# 9_pwm_out.net
KiCad netlist of a schematic drawn in Altium Designer
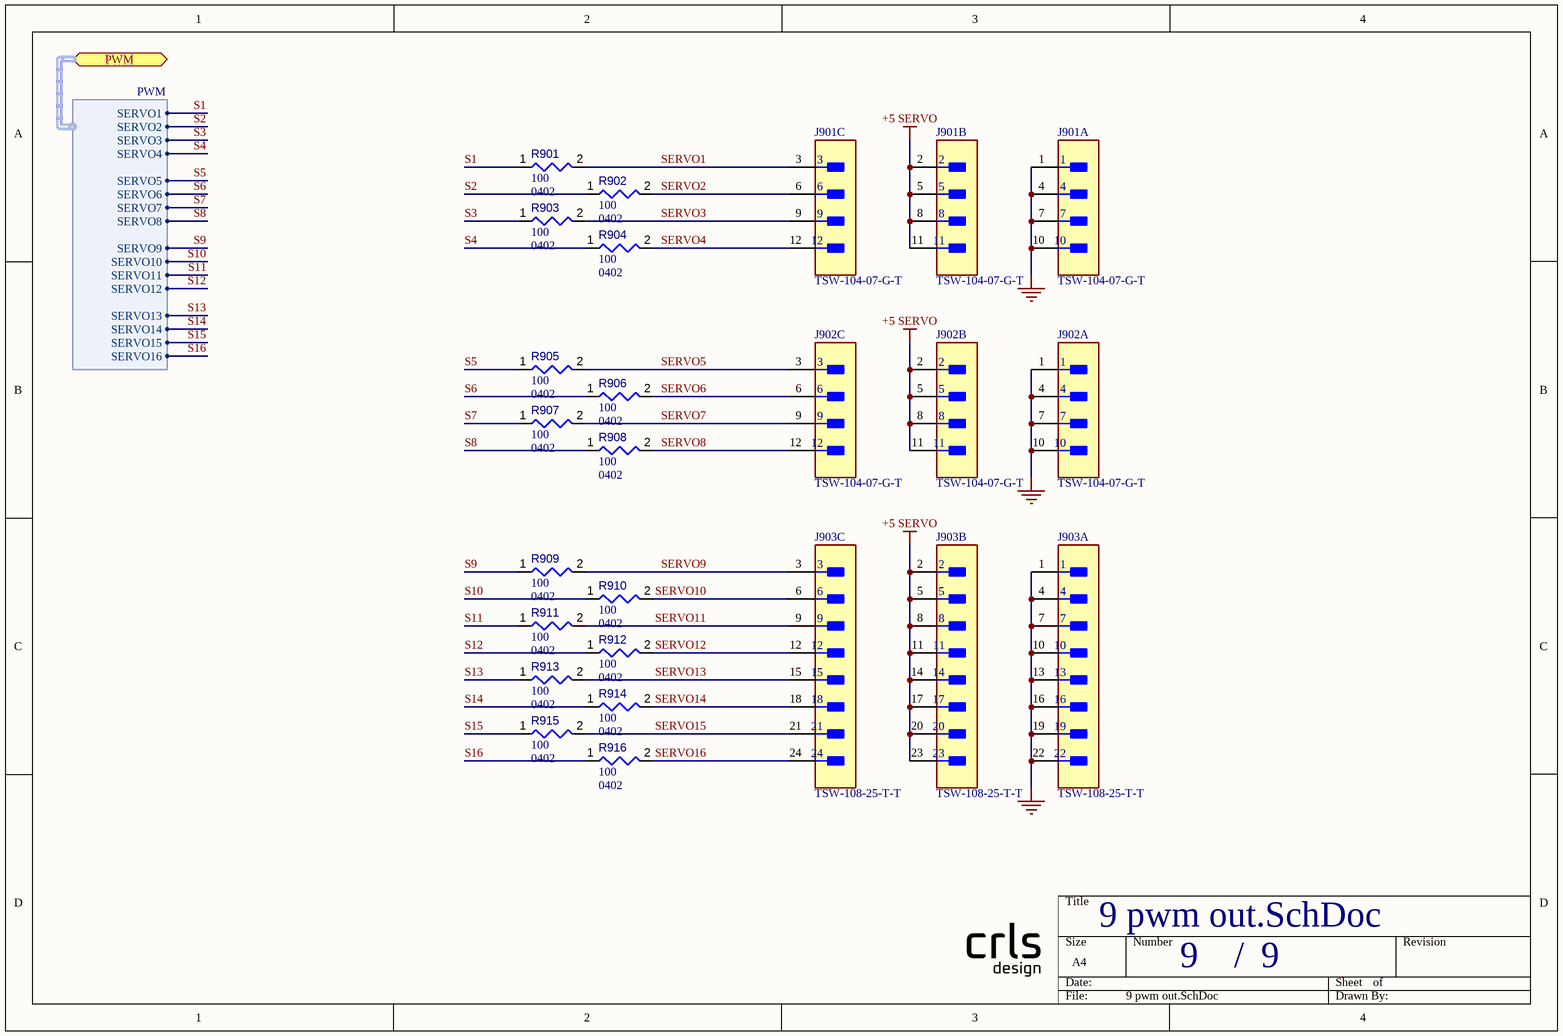
[diagram p0: 9 pwm out.SchDoc]

(export (version "E")
  (design (tool "Eeschema 10.0.6"))
  (components
    (comp (ref "J901")
      (value "TSW-104-07-G-T")
      (footprint "FP-TSW-104-07-G-T-MFG")
      (description "CONN HEADER VERT 12POS 2.54MM")
      (fields
        (field (name "MANUFACTURER") "Samtec")
        (field (name "OCTOPART") "https://octopart.com/tsw-104-07-g-t-samtec-8296723")
      )
      (libsource (lib "Altium Content Vault") (part "4835ffea529f644fb4232fae0277480"))
    )
    (comp (ref "J902")
      (value "TSW-104-07-G-T")
      (footprint "FP-TSW-104-07-G-T-MFG")
      (description "CONN HEADER VERT 12POS 2.54MM")
      (fields
        (field (name "MANUFACTURER") "Samtec")
        (field (name "OCTOPART") "https://octopart.com/tsw-104-07-g-t-samtec-8296723")
      )
      (libsource (lib "Altium Content Vault") (part "4835ffea529f644fb4232fae0277480"))
    )
    (comp (ref "J903")
      (value "TSW-108-25-T-T")
      (footprint "FP-TSW-108-25-T-T-MFG")
      (description "CONN HEADER VERT 24POS 2.54MM")
      (libsource (lib "Altium Content Vault") (part "1970d49fc78c71aba99bcf3589d2fd7"))
    )
    (comp (ref "R901")
      (value "100")
      (footprint "RESC0402(1005)_L")
      (description "Resistor")
      (fields
        (field (name "CASE/PACKAGE") "0402")
        (field (name "TOLERANCE") "1%")
        (field (name "Comment") "Resistors,0402,1%,100")
      )
      (libsource (lib "UBC Uncrewed Aircraft Systems") (part "RES-2"))
    )
    (comp (ref "R902")
      (value "100")
      (footprint "RESC0402(1005)_L")
      (description "Resistor")
      (fields
        (field (name "CASE/PACKAGE") "0402")
        (field (name "TOLERANCE") "1%")
        (field (name "Comment") "Resistors,0402,1%,100")
      )
      (libsource (lib "UBC Uncrewed Aircraft Systems") (part "RES-2"))
    )
    (comp (ref "R903")
      (value "100")
      (footprint "RESC0402(1005)_L")
      (description "Resistor")
      (fields
        (field (name "CASE/PACKAGE") "0402")
        (field (name "TOLERANCE") "1%")
        (field (name "Comment") "Resistors,0402,1%,100")
      )
      (libsource (lib "UBC Uncrewed Aircraft Systems") (part "RES-2"))
    )
    (comp (ref "R904")
      (value "100")
      (footprint "RESC0402(1005)_L")
      (description "Resistor")
      (fields
        (field (name "CASE/PACKAGE") "0402")
        (field (name "TOLERANCE") "1%")
        (field (name "Comment") "Resistors,0402,1%,100")
      )
      (libsource (lib "UBC Uncrewed Aircraft Systems") (part "RES-2"))
    )
    (comp (ref "R905")
      (value "100")
      (footprint "RESC0402(1005)_L")
      (description "Resistor")
      (fields
        (field (name "CASE/PACKAGE") "0402")
        (field (name "TOLERANCE") "1%")
        (field (name "Comment") "Resistors,0402,1%,100")
      )
      (libsource (lib "UBC Uncrewed Aircraft Systems") (part "RES-2"))
    )
    (comp (ref "R906")
      (value "100")
      (footprint "RESC0402(1005)_L")
      (description "Resistor")
      (fields
        (field (name "CASE/PACKAGE") "0402")
        (field (name "TOLERANCE") "1%")
        (field (name "Comment") "Resistors,0402,1%,100")
      )
      (libsource (lib "UBC Uncrewed Aircraft Systems") (part "RES-2"))
    )
    (comp (ref "R907")
      (value "100")
      (footprint "RESC0402(1005)_L")
      (description "Resistor")
      (fields
        (field (name "CASE/PACKAGE") "0402")
        (field (name "TOLERANCE") "1%")
        (field (name "Comment") "Resistors,0402,1%,100")
      )
      (libsource (lib "UBC Uncrewed Aircraft Systems") (part "RES-2"))
    )
    (comp (ref "R908")
      (value "100")
      (footprint "RESC0402(1005)_L")
      (description "Resistor")
      (fields
        (field (name "CASE/PACKAGE") "0402")
        (field (name "TOLERANCE") "1%")
        (field (name "Comment") "Resistors,0402,1%,100")
      )
      (libsource (lib "UBC Uncrewed Aircraft Systems") (part "RES-2"))
    )
    (comp (ref "R909")
      (value "100")
      (footprint "RESC0402(1005)_L")
      (description "Resistor")
      (fields
        (field (name "CASE/PACKAGE") "0402")
        (field (name "TOLERANCE") "1%")
        (field (name "Comment") "Resistors,0402,1%,100")
      )
      (libsource (lib "UBC Uncrewed Aircraft Systems") (part "RES-2"))
    )
    (comp (ref "R910")
      (value "100")
      (footprint "RESC0402(1005)_L")
      (description "Resistor")
      (fields
        (field (name "CASE/PACKAGE") "0402")
        (field (name "TOLERANCE") "1%")
        (field (name "Comment") "Resistors,0402,1%,100")
      )
      (libsource (lib "UBC Uncrewed Aircraft Systems") (part "RES-2"))
    )
    (comp (ref "R911")
      (value "100")
      (footprint "RESC0402(1005)_L")
      (description "Resistor")
      (fields
        (field (name "CASE/PACKAGE") "0402")
        (field (name "TOLERANCE") "1%")
        (field (name "Comment") "Resistors,0402,1%,100")
      )
      (libsource (lib "UBC Uncrewed Aircraft Systems") (part "RES-2"))
    )
    (comp (ref "R912")
      (value "100")
      (footprint "RESC0402(1005)_L")
      (description "Resistor")
      (fields
        (field (name "CASE/PACKAGE") "0402")
        (field (name "TOLERANCE") "1%")
        (field (name "Comment") "Resistors,0402,1%,100")
      )
      (libsource (lib "UBC Uncrewed Aircraft Systems") (part "RES-2"))
    )
    (comp (ref "R913")
      (value "100")
      (footprint "RESC0402(1005)_L")
      (description "Resistor")
      (fields
        (field (name "CASE/PACKAGE") "0402")
        (field (name "TOLERANCE") "1%")
        (field (name "Comment") "Resistors,0402,1%,100")
      )
      (libsource (lib "UBC Uncrewed Aircraft Systems") (part "RES-2"))
    )
    (comp (ref "R914")
      (value "100")
      (footprint "RESC0402(1005)_L")
      (description "Resistor")
      (fields
        (field (name "CASE/PACKAGE") "0402")
        (field (name "TOLERANCE") "1%")
        (field (name "Comment") "Resistors,0402,1%,100")
      )
      (libsource (lib "UBC Uncrewed Aircraft Systems") (part "RES-2"))
    )
    (comp (ref "R915")
      (value "100")
      (footprint "RESC0402(1005)_L")
      (description "Resistor")
      (fields
        (field (name "CASE/PACKAGE") "0402")
        (field (name "TOLERANCE") "1%")
        (field (name "Comment") "Resistors,0402,1%,100")
      )
      (libsource (lib "UBC Uncrewed Aircraft Systems") (part "RES-2"))
    )
    (comp (ref "R916")
      (value "100")
      (footprint "RESC0402(1005)_L")
      (description "Resistor")
      (fields
        (field (name "CASE/PACKAGE") "0402")
        (field (name "TOLERANCE") "1%")
        (field (name "Comment") "Resistors,0402,1%,100")
      )
      (libsource (lib "UBC Uncrewed Aircraft Systems") (part "RES-2"))
    )
  )
  (nets
    (net (code "2") (name "+5 SERVO") (class "Default")
      (node (ref "J901") (pin "11") (pinfunction "11_11") (pintype "passive"))
      (node (ref "J901") (pin "2") (pinfunction "2_2") (pintype "passive"))
      (node (ref "J901") (pin "5") (pinfunction "5_5") (pintype "passive"))
      (node (ref "J901") (pin "8") (pinfunction "8_8") (pintype "passive"))
      (node (ref "J902") (pin "11") (pinfunction "11_11") (pintype "passive"))
      (node (ref "J902") (pin "2") (pinfunction "2_2") (pintype "passive"))
      (node (ref "J902") (pin "5") (pinfunction "5_5") (pintype "passive"))
      (node (ref "J902") (pin "8") (pinfunction "8_8") (pintype "passive"))
      (node (ref "J903") (pin "11") (pinfunction "11_11") (pintype "passive"))
      (node (ref "J903") (pin "14") (pinfunction "14_14") (pintype "passive"))
      (node (ref "J903") (pin "17") (pinfunction "17_17") (pintype "passive"))
      (node (ref "J903") (pin "2") (pinfunction "2_2") (pintype "passive"))
      (node (ref "J903") (pin "20") (pinfunction "20_20") (pintype "passive"))
      (node (ref "J903") (pin "23") (pinfunction "23_23") (pintype "passive"))
      (node (ref "J903") (pin "5") (pinfunction "5_5") (pintype "passive"))
      (node (ref "J903") (pin "8") (pinfunction "8_8") (pintype "passive"))
    )
    (net (code "3") (name "/S1") (class "Default")
      (node (ref "R901") (pin "1") (pinfunction "1_1") (pintype "passive"))
    )
    (net (code "4") (name "/S2") (class "Default")
      (node (ref "R902") (pin "1") (pinfunction "1_1") (pintype "passive"))
    )
    (net (code "5") (name "/S3") (class "Default")
      (node (ref "R903") (pin "1") (pinfunction "1_1") (pintype "passive"))
    )
    (net (code "6") (name "/S4") (class "Default")
      (node (ref "R904") (pin "1") (pinfunction "1_1") (pintype "passive"))
    )
    (net (code "7") (name "/S5") (class "Default")
      (node (ref "R905") (pin "1") (pinfunction "1_1") (pintype "passive"))
    )
    (net (code "8") (name "/S6") (class "Default")
      (node (ref "R906") (pin "1") (pinfunction "1_1") (pintype "passive"))
    )
    (net (code "9") (name "/S7") (class "Default")
      (node (ref "R907") (pin "1") (pinfunction "1_1") (pintype "passive"))
    )
    (net (code "10") (name "/S8") (class "Default")
      (node (ref "R908") (pin "1") (pinfunction "1_1") (pintype "passive"))
    )
    (net (code "11") (name "/S9") (class "Default")
      (node (ref "R909") (pin "1") (pinfunction "1_1") (pintype "passive"))
    )
    (net (code "12") (name "/S10") (class "Default")
      (node (ref "R910") (pin "1") (pinfunction "1_1") (pintype "passive"))
    )
    (net (code "13") (name "/S11") (class "Default")
      (node (ref "R911") (pin "1") (pinfunction "1_1") (pintype "passive"))
    )
    (net (code "14") (name "/S12") (class "Default")
      (node (ref "R912") (pin "1") (pinfunction "1_1") (pintype "passive"))
    )
    (net (code "15") (name "/S13") (class "Default")
      (node (ref "R913") (pin "1") (pinfunction "1_1") (pintype "passive"))
    )
    (net (code "16") (name "/S14") (class "Default")
      (node (ref "R914") (pin "1") (pinfunction "1_1") (pintype "passive"))
    )
    (net (code "17") (name "/S15") (class "Default")
      (node (ref "R915") (pin "1") (pinfunction "1_1") (pintype "passive"))
    )
    (net (code "18") (name "/S16") (class "Default")
      (node (ref "R916") (pin "1") (pinfunction "1_1") (pintype "passive"))
    )
    (net (code "19") (name "/SERVO1") (class "Default")
      (node (ref "J901") (pin "3") (pinfunction "3_3") (pintype "passive"))
      (node (ref "R901") (pin "2") (pinfunction "2_2") (pintype "passive"))
    )
    (net (code "20") (name "/SERVO2") (class "Default")
      (node (ref "J901") (pin "6") (pinfunction "6_6") (pintype "passive"))
      (node (ref "R902") (pin "2") (pinfunction "2_2") (pintype "passive"))
    )
    (net (code "21") (name "/SERVO3") (class "Default")
      (node (ref "J901") (pin "9") (pinfunction "9_9") (pintype "passive"))
      (node (ref "R903") (pin "2") (pinfunction "2_2") (pintype "passive"))
    )
    (net (code "22") (name "/SERVO4") (class "Default")
      (node (ref "J901") (pin "12") (pinfunction "12_12") (pintype "passive"))
      (node (ref "R904") (pin "2") (pinfunction "2_2") (pintype "passive"))
    )
    (net (code "23") (name "/SERVO5") (class "Default")
      (node (ref "J902") (pin "3") (pinfunction "3_3") (pintype "passive"))
      (node (ref "R905") (pin "2") (pinfunction "2_2") (pintype "passive"))
    )
    (net (code "24") (name "/SERVO6") (class "Default")
      (node (ref "J902") (pin "6") (pinfunction "6_6") (pintype "passive"))
      (node (ref "R906") (pin "2") (pinfunction "2_2") (pintype "passive"))
    )
    (net (code "25") (name "/SERVO7") (class "Default")
      (node (ref "J902") (pin "9") (pinfunction "9_9") (pintype "passive"))
      (node (ref "R907") (pin "2") (pinfunction "2_2") (pintype "passive"))
    )
    (net (code "26") (name "/SERVO8") (class "Default")
      (node (ref "J902") (pin "12") (pinfunction "12_12") (pintype "passive"))
      (node (ref "R908") (pin "2") (pinfunction "2_2") (pintype "passive"))
    )
    (net (code "27") (name "/SERVO9") (class "Default")
      (node (ref "J903") (pin "3") (pinfunction "3_3") (pintype "passive"))
      (node (ref "R909") (pin "2") (pinfunction "2_2") (pintype "passive"))
    )
    (net (code "28") (name "/SERVO10") (class "Default")
      (node (ref "J903") (pin "6") (pinfunction "6_6") (pintype "passive"))
      (node (ref "R910") (pin "2") (pinfunction "2_2") (pintype "passive"))
    )
    (net (code "29") (name "/SERVO11") (class "Default")
      (node (ref "J903") (pin "9") (pinfunction "9_9") (pintype "passive"))
      (node (ref "R911") (pin "2") (pinfunction "2_2") (pintype "passive"))
    )
    (net (code "30") (name "/SERVO12") (class "Default")
      (node (ref "J903") (pin "12") (pinfunction "12_12") (pintype "passive"))
      (node (ref "R912") (pin "2") (pinfunction "2_2") (pintype "passive"))
    )
    (net (code "31") (name "/SERVO13") (class "Default")
      (node (ref "J903") (pin "15") (pinfunction "15_15") (pintype "passive"))
      (node (ref "R913") (pin "2") (pinfunction "2_2") (pintype "passive"))
    )
    (net (code "32") (name "/SERVO14") (class "Default")
      (node (ref "J903") (pin "18") (pinfunction "18_18") (pintype "passive"))
      (node (ref "R914") (pin "2") (pinfunction "2_2") (pintype "passive"))
    )
    (net (code "33") (name "/SERVO15") (class "Default")
      (node (ref "J903") (pin "21") (pinfunction "21_21") (pintype "passive"))
      (node (ref "R915") (pin "2") (pinfunction "2_2") (pintype "passive"))
    )
    (net (code "34") (name "/SERVO16") (class "Default")
      (node (ref "J903") (pin "24") (pinfunction "24_24") (pintype "passive"))
      (node (ref "R916") (pin "2") (pinfunction "2_2") (pintype "passive"))
    )
    (net (code "36") (name "GND") (class "Default")
      (node (ref "J901") (pin "1") (pinfunction "1_1") (pintype "passive"))
      (node (ref "J901") (pin "10") (pinfunction "10_10") (pintype "passive"))
      (node (ref "J901") (pin "4") (pinfunction "4_4") (pintype "passive"))
      (node (ref "J901") (pin "7") (pinfunction "7_7") (pintype "passive"))
      (node (ref "J902") (pin "1") (pinfunction "1_1") (pintype "passive"))
      (node (ref "J902") (pin "10") (pinfunction "10_10") (pintype "passive"))
      (node (ref "J902") (pin "4") (pinfunction "4_4") (pintype "passive"))
      (node (ref "J902") (pin "7") (pinfunction "7_7") (pintype "passive"))
      (node (ref "J903") (pin "1") (pinfunction "1_1") (pintype "passive"))
      (node (ref "J903") (pin "10") (pinfunction "10_10") (pintype "passive"))
      (node (ref "J903") (pin "13") (pinfunction "13_13") (pintype "passive"))
      (node (ref "J903") (pin "16") (pinfunction "16_16") (pintype "passive"))
      (node (ref "J903") (pin "19") (pinfunction "19_19") (pintype "passive"))
      (node (ref "J903") (pin "22") (pinfunction "22_22") (pintype "passive"))
      (node (ref "J903") (pin "4") (pinfunction "4_4") (pintype "passive"))
      (node (ref "J903") (pin "7") (pinfunction "7_7") (pintype "passive"))
    )
  )
)
